# Main.net
KiCad netlist of a schematic drawn in Altium Designer
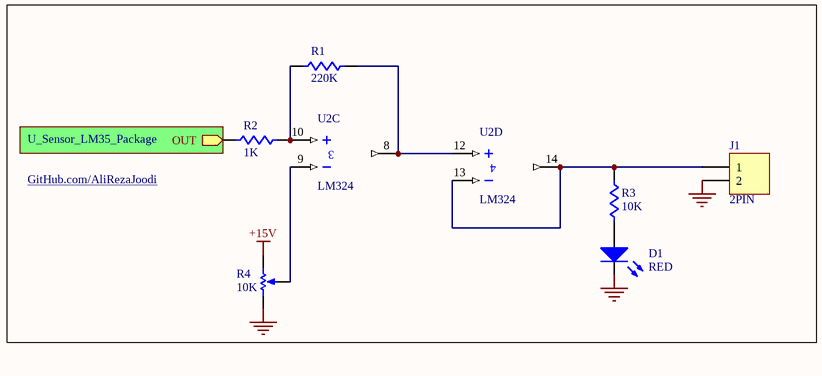
[diagram p0: Main.SchDoc]

(export (version "E")
  (design (tool "Eeschema 10.0.6"))
  (components
    (comp (ref "D1")
      (value "RED")
      (footprint "LED-5mm_Red")
      (description "Typical INFRARED GaAs LED")
      (fields (field (name "MANUFACTURER") "Generic Components") (field (name "PUBLISHER") "Altium Limited"))
      (libsource (lib "Miscellaneous Devices") (part "LED"))
    )
    (comp (ref "J1")
      (value "2PIN")
      (footprint "Fonics_2PIN_1")
      (description "Header, 2-Pin")
      (fields (field (name "MANUFACTURER") "Generic Components") (field (name "PUBLISHER") "Altium Limited"))
      (libsource (lib "Miscellaneous Connectors") (part "Header 2"))
    )
    (comp (ref "R1")
      (value "220K")
      (footprint "AXIAL-0.4")
      (description "Resistor")
      (fields (field (name "MANUFACTURER") "Generic Components") (field (name "PUBLISHER") "Altium Limited"))
      (libsource (lib "Miscellaneous Devices") (part "Res1"))
    )
    (comp (ref "R2")
      (value "1K")
      (footprint "AXIAL-0.4")
      (description "Resistor")
      (fields (field (name "MANUFACTURER") "Generic Components") (field (name "PUBLISHER") "Altium Limited"))
      (libsource (lib "Miscellaneous Devices") (part "Res1"))
    )
    (comp (ref "R3")
      (value "10K")
      (footprint "AXIAL-0.4")
      (description "Resistor")
      (fields (field (name "MANUFACTURER") "Generic Components") (field (name "PUBLISHER") "Altium Limited"))
      (libsource (lib "Miscellaneous Devices") (part "Res1"))
    )
    (comp (ref "R4")
      (value "10K")
      (footprint "VR4_")
      (description "Potentiometer")
      (fields (field (name "MANUFACTURER") "Generic Components") (field (name "PUBLISHER") "Altium Limited"))
      (libsource (lib "my Libraries") (part "RPot1"))
    )
    (comp (ref "U2")
      (value "LM324")
      (footprint "646-06")
      (description "Quad Low-Power Operational Amplifier")
      (fields (field (name "PUBLISHER") "Altium Limited"))
      (libsource (lib "my Libraries") (part "LM324"))
    )
  )
  (nets
    (net (code "1") (name "+15V") (class "Default")
      (node (ref "R4") (pin "2") (pinfunction "BOT_2") (pintype "passive"))
    )
    (net (code "2") (name "/OUT") (class "Default")
      (node (ref "R2") (pin "1") (pinfunction "1_1") (pintype "passive"))
    )
    (net (code "3") (name "GND") (class "Default")
      (node (ref "D1") (pin "2") (pinfunction "K_2") (pintype "passive"))
      (node (ref "J1") (pin "2") (pinfunction "2_2") (pintype "passive"))
      (node (ref "R4") (pin "1") (pinfunction "TOP_1") (pintype "passive"))
    )
    (net (code "4") (name "Net-(D1-A)") (class "Default")
      (node (ref "D1") (pin "1") (pinfunction "A_1") (pintype "passive"))
      (node (ref "R3") (pin "2") (pinfunction "2_2") (pintype "passive"))
    )
    (net (code "5") (name "Net-(R4-TAP)") (class "Default")
      (node (ref "R4") (pin "3") (pinfunction "TAP_3") (pintype "passive"))
      (node (ref "U2") (pin "9") (pinfunction "IN-_9") (pintype "input"))
    )
    (net (code "6") (name "Net-(U2C-IN+)") (class "Default")
      (node (ref "R1") (pin "1") (pinfunction "1_1") (pintype "passive"))
      (node (ref "R2") (pin "2") (pinfunction "2_2") (pintype "passive"))
      (node (ref "U2") (pin "10") (pinfunction "IN+_10") (pintype "input"))
    )
    (net (code "7") (name "Net-(U2C-OUT)") (class "Default")
      (node (ref "R1") (pin "2") (pinfunction "2_2") (pintype "passive"))
      (node (ref "U2") (pin "12") (pinfunction "IN+_12") (pintype "input"))
      (node (ref "U2") (pin "8") (pinfunction "OUT_8") (pintype "output"))
    )
    (net (code "8") (name "Net-(U2D-IN-)") (class "Default")
      (node (ref "J1") (pin "1") (pinfunction "1_1") (pintype "passive"))
      (node (ref "R3") (pin "1") (pinfunction "1_1") (pintype "passive"))
      (node (ref "U2") (pin "13") (pinfunction "IN-_13") (pintype "input"))
      (node (ref "U2") (pin "14") (pinfunction "OUT_14") (pintype "output"))
    )
  )
)
